# Token1.net
KiCad netlist of a schematic drawn in EAGLE
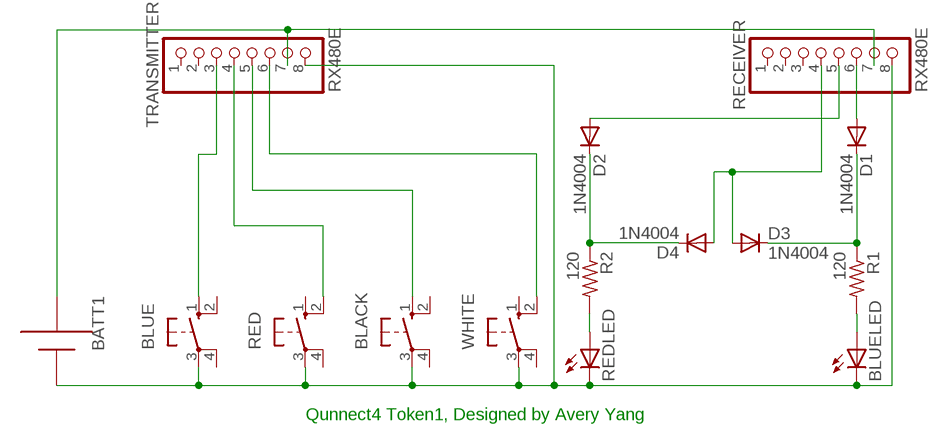
[diagram p0: schematic, sheet 1]

(export (version "E")
  (design (tool "Eeschema 10.0.6"))
  (components
    (comp (ref "BATT1")
      (value "AAA")
      (footprint "eagle-import:12BH412")
      (libsource (lib "eagle-import") (part "AAA"))
    )
    (comp (ref "BLACK")
      (value "10-XX")
      (footprint "eagle-import:B3F-10XX")
      (fields (field (name "MPN") "B3F-1000"))
      (libsource (lib "eagle-import") (part "10-XX"))
    )
    (comp (ref "BLUE")
      (value "10-XX")
      (footprint "eagle-import:B3F-10XX")
      (fields (field (name "MPN") "B3F-1000"))
      (libsource (lib "eagle-import") (part "10-XX"))
    )
    (comp (ref "BLUELED")
      (value "LED5MM")
      (footprint "eagle-import:LED5MM")
      (libsource (lib "eagle-import") (part "LED5MM"))
    )
    (comp (ref "D1")
      (value "1N4004")
      (footprint "eagle-import:DO41-10")
      (libsource (lib "eagle-import") (part "1N4004"))
    )
    (comp (ref "D2")
      (value "1N4004")
      (footprint "eagle-import:DO41-10")
      (libsource (lib "eagle-import") (part "1N4004"))
    )
    (comp (ref "D3")
      (value "1N4004")
      (footprint "eagle-import:DO41-10")
      (libsource (lib "eagle-import") (part "1N4004"))
    )
    (comp (ref "D4")
      (value "1N4004")
      (footprint "eagle-import:DO41-10")
      (libsource (lib "eagle-import") (part "1N4004"))
    )
    (comp (ref "R1")
      (value "120")
      (footprint "eagle-import:0207_10")
      (libsource (lib "eagle-import") (part "R-US_0207/10"))
    )
    (comp (ref "R2")
      (value "120")
      (footprint "eagle-import:0207_10")
      (libsource (lib "eagle-import") (part "R-US_0207/10"))
    )
    (comp (ref "RECEIVER")
      (value "RX480E")
      (footprint "eagle-import:1X08")
      (libsource (lib "eagle-import") (part "PINHD-1X8"))
    )
    (comp (ref "RED")
      (value "10-XX")
      (footprint "eagle-import:B3F-10XX")
      (fields (field (name "MPN") "B3F-1000"))
      (libsource (lib "eagle-import") (part "10-XX"))
    )
    (comp (ref "REDLED")
      (value "LED5MM")
      (footprint "eagle-import:LED5MM")
      (libsource (lib "eagle-import") (part "LED5MM"))
    )
    (comp (ref "TRANSMITTER")
      (value "RX480E")
      (footprint "eagle-import:1X08")
      (libsource (lib "eagle-import") (part "PINHD-1X8"))
    )
    (comp (ref "WHITE")
      (value "10-XX")
      (footprint "eagle-import:B3F-10XX")
      (fields (field (name "MPN") "B3F-1000"))
      (libsource (lib "eagle-import") (part "10-XX"))
    )
  )
  (nets
    (net (code "1") (name "Net-(BATT1-Pad-)") (class "Default")
      (node (ref "BATT1") (pin "-") (pinfunction "-_-") (pintype "bidirectional"))
      (node (ref "RECEIVER") (pin "7") (pinfunction "7_7") (pintype "passive"))
      (node (ref "TRANSMITTER") (pin "7") (pinfunction "7_7") (pintype "passive"))
    )
    (net (code "2") (name "Net-(BLACK-P)") (class "Default")
      (node (ref "BATT1") (pin "+") (pinfunction "+_+") (pintype "bidirectional"))
      (node (ref "BLACK") (pin "3") (pinfunction "P_3") (pintype "passive"))
      (node (ref "BLUE") (pin "3") (pinfunction "P_3") (pintype "passive"))
      (node (ref "BLUELED") (pin "K") (pinfunction "C_K") (pintype "passive"))
      (node (ref "RECEIVER") (pin "8") (pinfunction "8_8") (pintype "passive"))
      (node (ref "RED") (pin "3") (pinfunction "P_3") (pintype "passive"))
      (node (ref "REDLED") (pin "K") (pinfunction "C_K") (pintype "passive"))
      (node (ref "TRANSMITTER") (pin "8") (pinfunction "8_8") (pintype "passive"))
      (node (ref "WHITE") (pin "3") (pinfunction "P_3") (pintype "passive"))
    )
    (net (code "3") (name "Net-(BLACK-S)") (class "Default")
      (node (ref "BLACK") (pin "1") (pinfunction "S_1") (pintype "passive"))
      (node (ref "TRANSMITTER") (pin "5") (pinfunction "5_5") (pintype "passive"))
    )
    (net (code "4") (name "Net-(BLUE-S)") (class "Default")
      (node (ref "BLUE") (pin "1") (pinfunction "S_1") (pintype "passive"))
      (node (ref "TRANSMITTER") (pin "3") (pinfunction "3_3") (pintype "passive"))
    )
    (net (code "5") (name "Net-(BLUELED-PadA)") (class "Default")
      (node (ref "BLUELED") (pin "A") (pinfunction "A_A") (pintype "passive"))
      (node (ref "R1") (pin "2") (pinfunction "2_2") (pintype "passive"))
    )
    (net (code "6") (name "Net-(D1-PadA)") (class "Default")
      (node (ref "D1") (pin "A") (pinfunction "A_A") (pintype "passive"))
      (node (ref "RECEIVER") (pin "6") (pinfunction "6_6") (pintype "passive"))
    )
    (net (code "7") (name "Net-(D1-PadC)") (class "Default")
      (node (ref "D1") (pin "C") (pinfunction "C_C") (pintype "passive"))
      (node (ref "D3") (pin "C") (pinfunction "C_C") (pintype "passive"))
      (node (ref "R1") (pin "1") (pinfunction "1_1") (pintype "passive"))
    )
    (net (code "8") (name "Net-(D2-PadA)") (class "Default")
      (node (ref "D2") (pin "A") (pinfunction "A_A") (pintype "passive"))
      (node (ref "RECEIVER") (pin "5") (pinfunction "5_5") (pintype "passive"))
    )
    (net (code "9") (name "Net-(D2-PadC)") (class "Default")
      (node (ref "D2") (pin "C") (pinfunction "C_C") (pintype "passive"))
      (node (ref "D4") (pin "C") (pinfunction "C_C") (pintype "passive"))
      (node (ref "R2") (pin "1") (pinfunction "1_1") (pintype "passive"))
    )
    (net (code "10") (name "Net-(D3-PadA)") (class "Default")
      (node (ref "D3") (pin "A") (pinfunction "A_A") (pintype "passive"))
      (node (ref "D4") (pin "A") (pinfunction "A_A") (pintype "passive"))
      (node (ref "RECEIVER") (pin "4") (pinfunction "4_4") (pintype "passive"))
    )
    (net (code "11") (name "Net-(R2-Pad2)") (class "Default")
      (node (ref "R2") (pin "2") (pinfunction "2_2") (pintype "passive"))
      (node (ref "REDLED") (pin "A") (pinfunction "A_A") (pintype "passive"))
    )
    (net (code "12") (name "Net-(RED-S1)") (class "Default")
      (node (ref "RED") (pin "2") (pinfunction "S1_2") (pintype "passive"))
      (node (ref "TRANSMITTER") (pin "4") (pinfunction "4_4") (pintype "passive"))
    )
    (net (code "13") (name "Net-(WHITE-S1)") (class "Default")
      (node (ref "TRANSMITTER") (pin "6") (pinfunction "6_6") (pintype "passive"))
      (node (ref "WHITE") (pin "2") (pinfunction "S1_2") (pintype "passive"))
    )
    (net (code "14") (name "unconnected-(BLACK-P1-Pad4)") (class "Default")
      (node (ref "BLACK") (pin "4") (pinfunction "P1_4") (pintype "passive"))
    )
    (net (code "15") (name "unconnected-(BLACK-S1-Pad2)") (class "Default")
      (node (ref "BLACK") (pin "2") (pinfunction "S1_2") (pintype "passive"))
    )
    (net (code "16") (name "unconnected-(BLUE-P1-Pad4)") (class "Default")
      (node (ref "BLUE") (pin "4") (pinfunction "P1_4") (pintype "passive"))
    )
    (net (code "17") (name "unconnected-(BLUE-S1-Pad2)") (class "Default")
      (node (ref "BLUE") (pin "2") (pinfunction "S1_2") (pintype "passive"))
    )
    (net (code "18") (name "unconnected-(RECEIVER-Pad1)") (class "Default")
      (node (ref "RECEIVER") (pin "1") (pinfunction "1_1") (pintype "passive"))
    )
    (net (code "19") (name "unconnected-(RECEIVER-Pad2)") (class "Default")
      (node (ref "RECEIVER") (pin "2") (pinfunction "2_2") (pintype "passive"))
    )
    (net (code "20") (name "unconnected-(RECEIVER-Pad3)") (class "Default")
      (node (ref "RECEIVER") (pin "3") (pinfunction "3_3") (pintype "passive"))
    )
    (net (code "21") (name "unconnected-(RED-P1-Pad4)") (class "Default")
      (node (ref "RED") (pin "4") (pinfunction "P1_4") (pintype "passive"))
    )
    (net (code "22") (name "unconnected-(RED-S-Pad1)") (class "Default")
      (node (ref "RED") (pin "1") (pinfunction "S_1") (pintype "passive"))
    )
    (net (code "23") (name "unconnected-(TRANSMITTER-Pad1)") (class "Default")
      (node (ref "TRANSMITTER") (pin "1") (pinfunction "1_1") (pintype "passive"))
    )
    (net (code "24") (name "unconnected-(TRANSMITTER-Pad2)") (class "Default")
      (node (ref "TRANSMITTER") (pin "2") (pinfunction "2_2") (pintype "passive"))
    )
    (net (code "25") (name "unconnected-(WHITE-P1-Pad4)") (class "Default")
      (node (ref "WHITE") (pin "4") (pinfunction "P1_4") (pintype "passive"))
    )
    (net (code "26") (name "unconnected-(WHITE-S-Pad1)") (class "Default")
      (node (ref "WHITE") (pin "1") (pinfunction "S_1") (pintype "passive"))
    )
  )
)
